# main_module.net
KiCad netlist of a schematic drawn in EAGLE
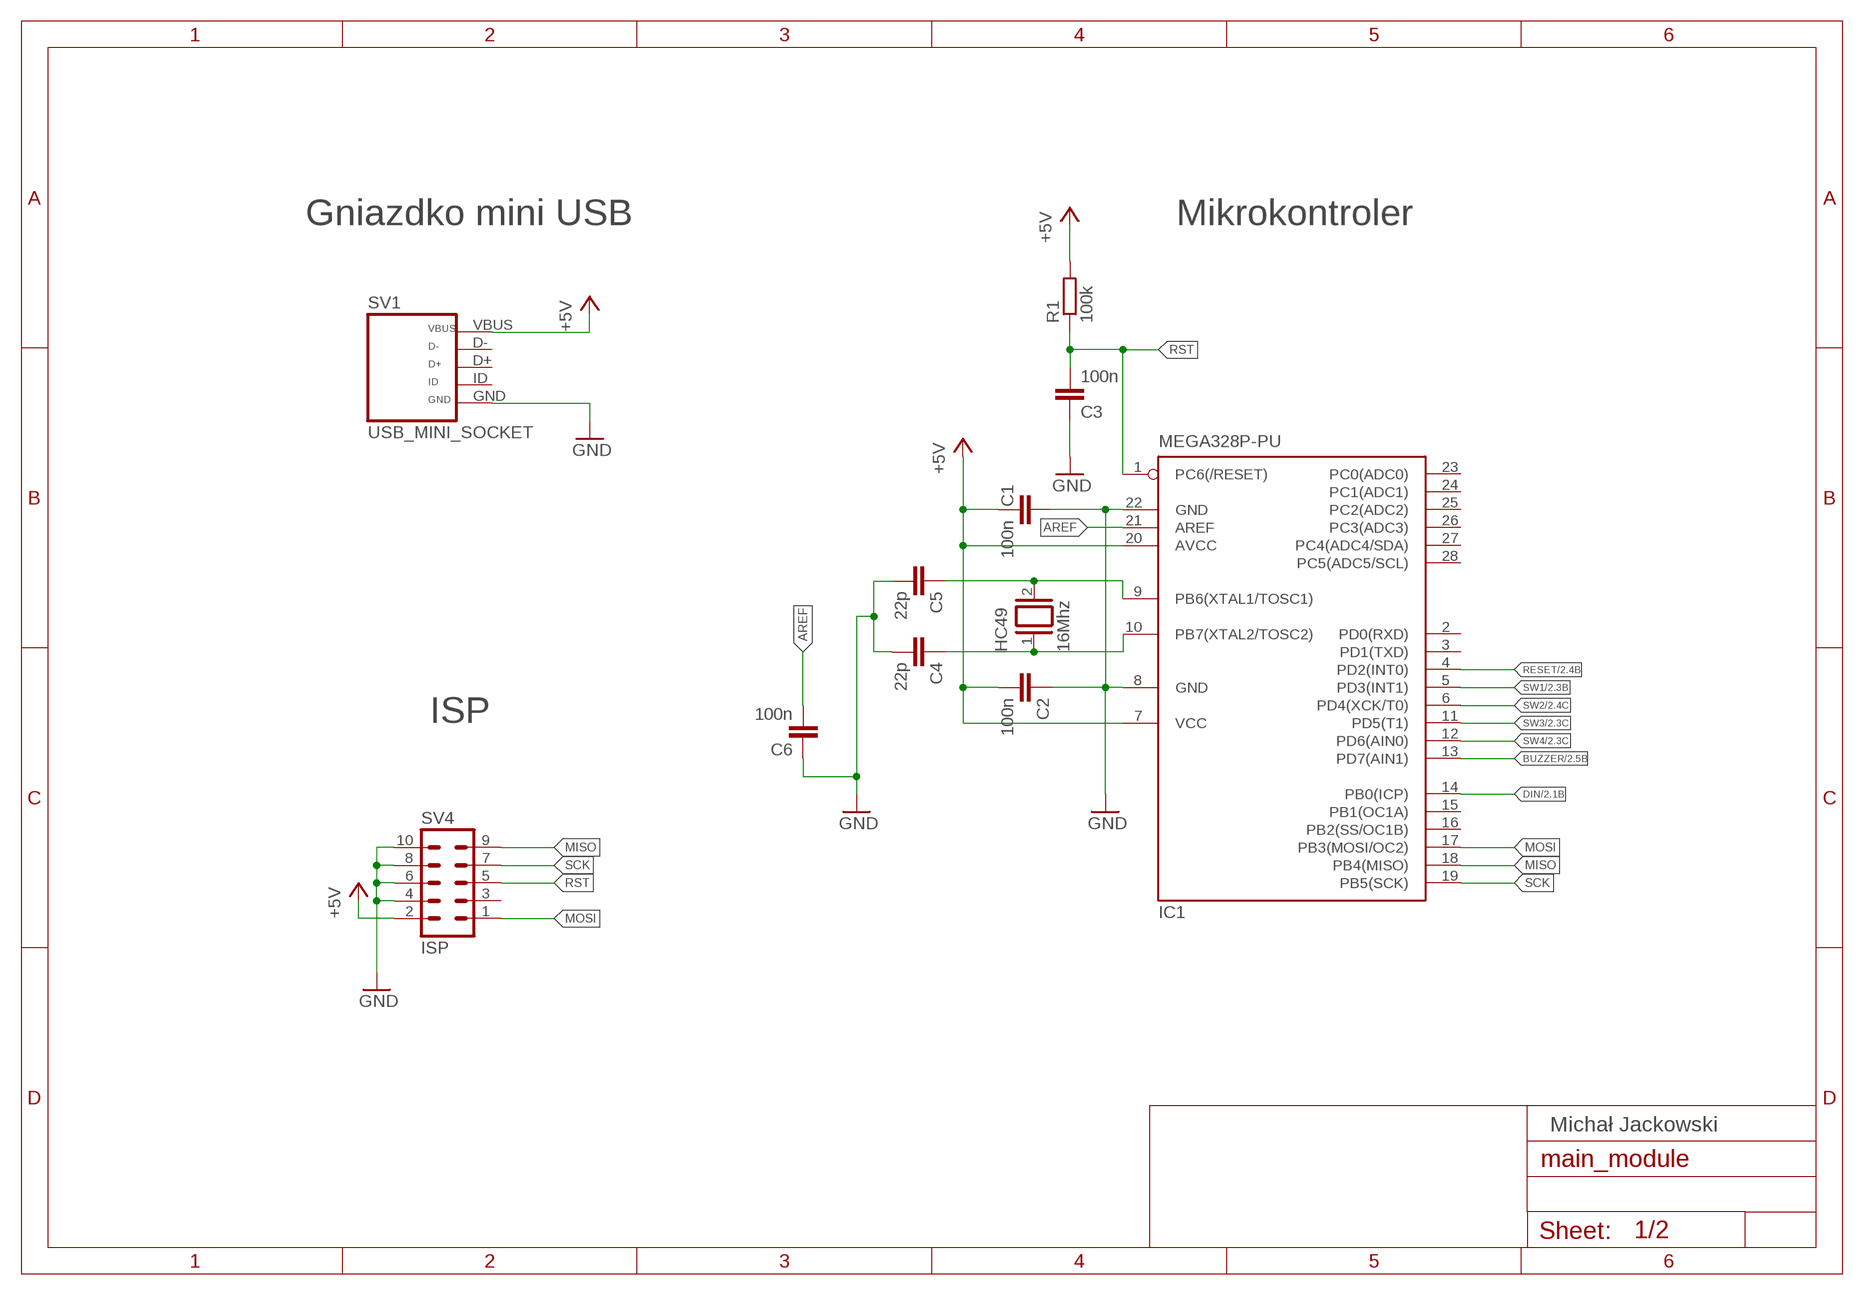
[diagram p0: schematic, sheet 1]
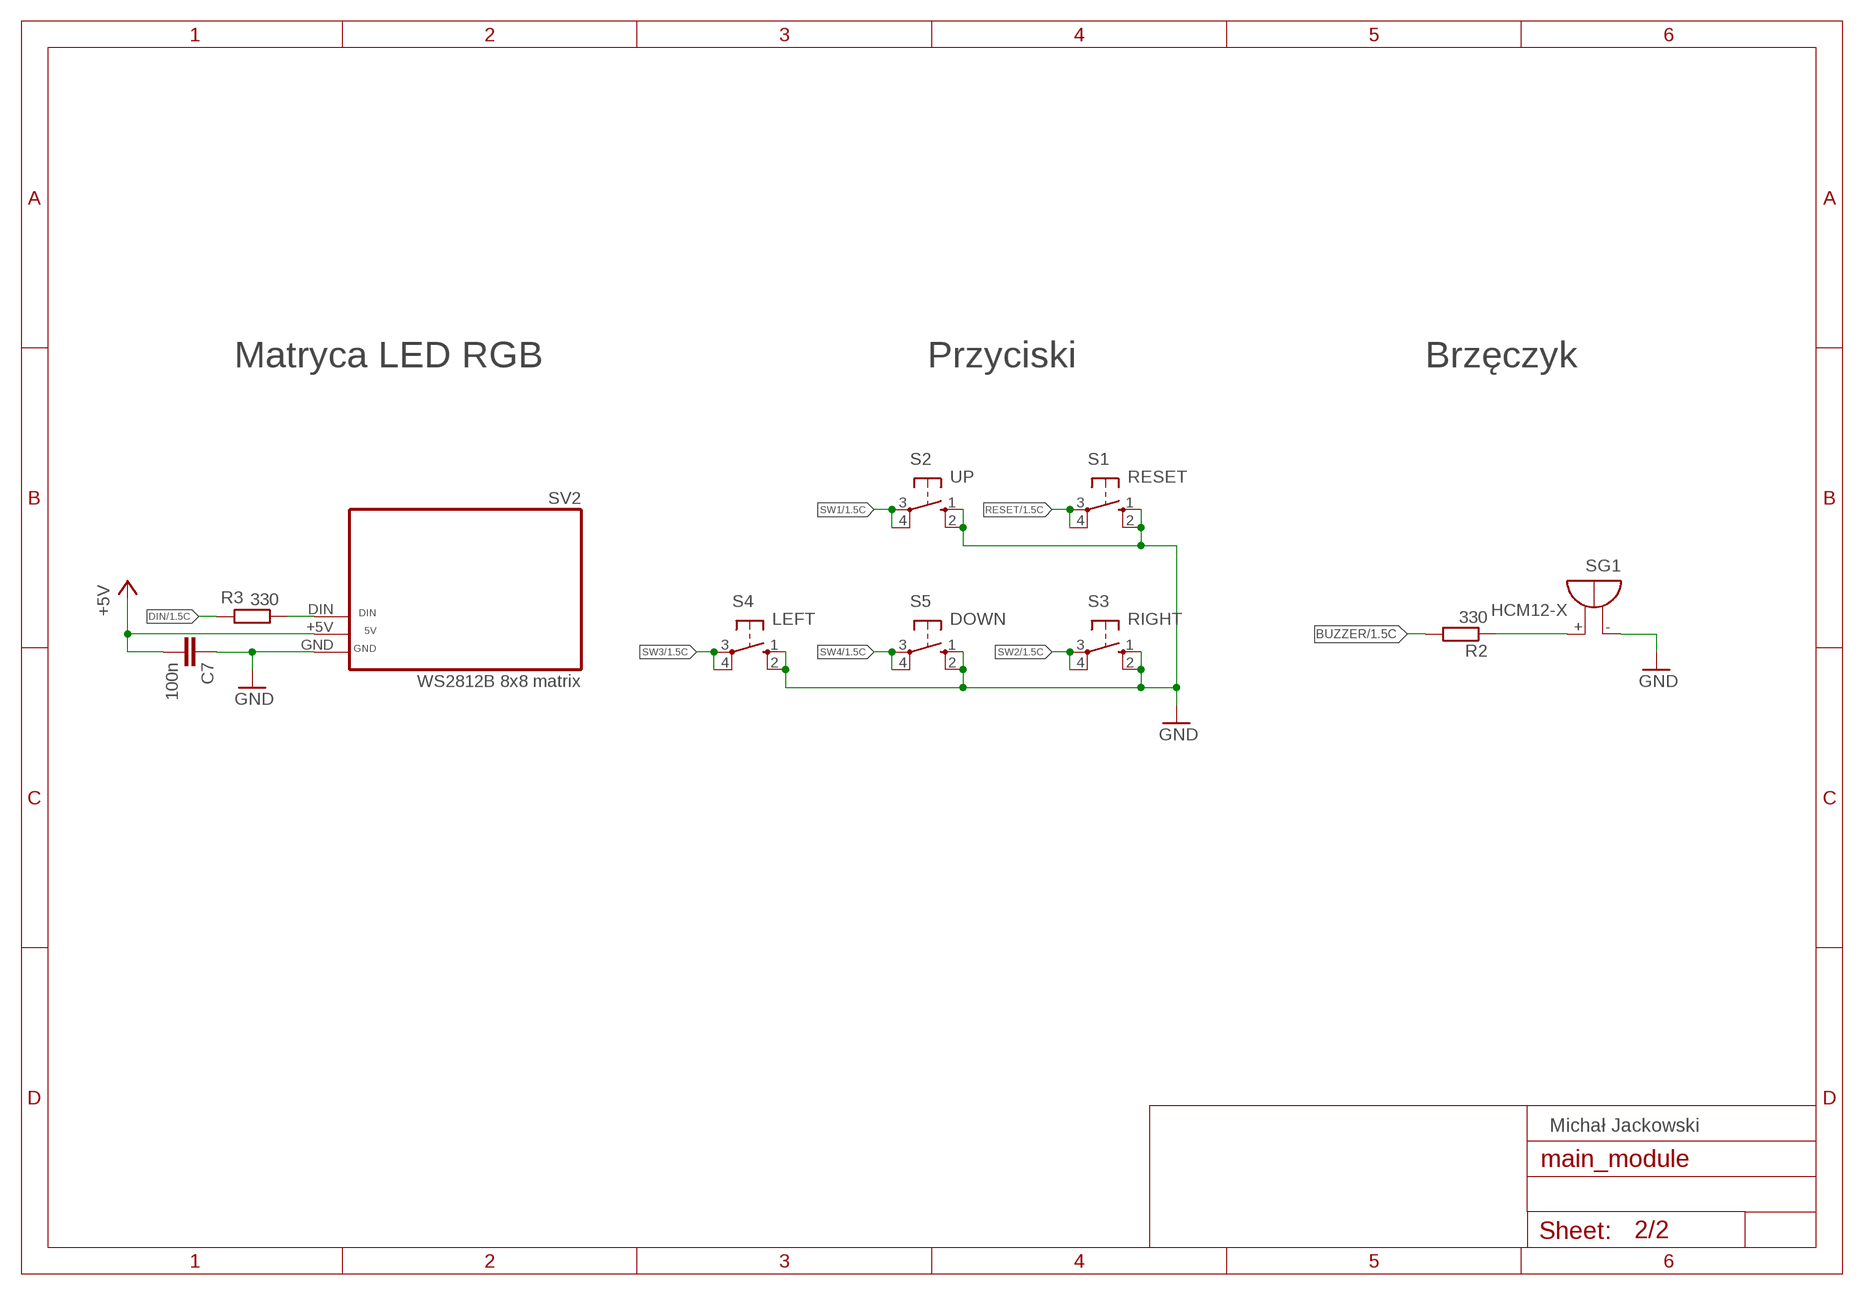
[diagram p1: schematic, sheet 2]

(export (version "E")
  (design (tool "Eeschema 10.0.6"))
  (components
    (comp (ref "C1")
      (value "100n")
      (footprint "eagle-import:C025-040X050")
      (libsource (lib "eagle-import") (part "C-EU025-040X050"))
    )
    (comp (ref "C2")
      (value "100n")
      (footprint "eagle-import:C025-040X050")
      (libsource (lib "eagle-import") (part "C-EU025-040X050"))
    )
    (comp (ref "C3")
      (value "100n")
      (footprint "eagle-import:C025-040X050")
      (libsource (lib "eagle-import") (part "C-EU025-040X050"))
    )
    (comp (ref "C4")
      (value "22p")
      (footprint "eagle-import:C025-040X050")
      (libsource (lib "eagle-import") (part "C-EU025-040X050"))
    )
    (comp (ref "C5")
      (value "22p")
      (footprint "eagle-import:C025-040X050")
      (libsource (lib "eagle-import") (part "C-EU025-040X050"))
    )
    (comp (ref "C6")
      (value "100n")
      (footprint "eagle-import:C025-040X050")
      (libsource (lib "eagle-import") (part "C-EU025-040X050"))
    )
    (comp (ref "IC1")
      (value "MEGA328P-PU")
      (footprint "eagle-import:DIL28-3")
      (libsource (lib "eagle-import") (part "MEGA328P-PU"))
    )
    (comp (ref "Q1")
      (value "16Mhz")
      (footprint "eagle-import:Q")
      (libsource (lib "eagle-import") (part "XTAL"))
    )
    (comp (ref "R1")
      (value "100k")
      (footprint "eagle-import:0204_7")
      (libsource (lib "eagle-import") (part "R-EU_0204/7"))
    )
    (comp (ref "SV1")
      (value "USB_MINI_SOCKET")
      (footprint "eagle-import:FE05-1")
      (libsource (lib "eagle-import") (part "USB_MINI_SOCKETGNIAZDO5PINFE"))
    )
    (comp (ref "SV4")
      (value "ISP")
      (footprint "eagle-import:ML10L")
      (libsource (lib "eagle-import") (part "ML10L"))
    )
    (comp (ref "C7")
      (value "100n")
      (footprint "eagle-import:C025-040X050")
      (libsource (lib "eagle-import") (part "C-EU025-040X050"))
    )
    (comp (ref "R2")
      (value "330")
      (footprint "eagle-import:0204_7")
      (libsource (lib "eagle-import") (part "R-EU_0204/7"))
    )
    (comp (ref "R3")
      (value "330")
      (footprint "eagle-import:0204_7")
      (libsource (lib "eagle-import") (part "R-EU_0204/7"))
    )
    (comp (ref "S1")
      (value "RESET")
      (footprint "eagle-import:B3F-40XX")
      (fields (field (name "MF") "OMRON COMPONENTS USA") (field (name "MPN") "B3F-4000"))
      (libsource (lib "eagle-import") (part "40-XX"))
    )
    (comp (ref "S2")
      (value "UP")
      (footprint "eagle-import:B3F-40XX")
      (fields (field (name "MF") "OMRON COMPONENTS USA") (field (name "MPN") "B3F-4000"))
      (libsource (lib "eagle-import") (part "40-XX"))
    )
    (comp (ref "S3")
      (value "RIGHT")
      (footprint "eagle-import:B3F-40XX")
      (fields (field (name "MF") "OMRON COMPONENTS USA") (field (name "MPN") "B3F-4000"))
      (libsource (lib "eagle-import") (part "40-XX"))
    )
    (comp (ref "S4")
      (value "LEFT")
      (footprint "eagle-import:B3F-40XX")
      (fields (field (name "MF") "OMRON COMPONENTS USA") (field (name "MPN") "B3F-4000"))
      (libsource (lib "eagle-import") (part "40-XX"))
    )
    (comp (ref "S5")
      (value "DOWN")
      (footprint "eagle-import:B3F-40XX")
      (fields (field (name "MF") "OMRON COMPONENTS USA") (field (name "MPN") "B3F-4000"))
      (libsource (lib "eagle-import") (part "40-XX"))
    )
    (comp (ref "SG1")
      (value "HCM12-X")
      (footprint "eagle-import:F_QMBIII")
      (libsource (lib "eagle-import") (part "HCM12-X"))
    )
    (comp (ref "SV2")
      (value "RGB_MATRIX_SOCKET")
      (footprint "eagle-import:MA03-1")
      (libsource (lib "eagle-import") (part "RGB_MATRIX_CONNECTOR"))
    )
  )
  (nets
    (net (code "1") (name "+5V") (class "Default")
      (node (ref "C1") (pin "2") (pinfunction "2_2") (pintype "passive"))
      (node (ref "C2") (pin "2") (pinfunction "2_2") (pintype "passive"))
      (node (ref "C7") (pin "2") (pinfunction "2_2") (pintype "passive"))
      (node (ref "IC1") (pin "20") (pinfunction "AVCC_20") (pintype "power_in"))
      (node (ref "IC1") (pin "7") (pinfunction "VCC_7") (pintype "power_in"))
      (node (ref "R1") (pin "2") (pinfunction "2_2") (pintype "passive"))
      (node (ref "SV1") (pin "VBUS") (pinfunction "VBUS_VBUS") (pintype "passive"))
      (node (ref "SV2") (pin "+5V") (pinfunction "5V_+5V") (pintype "passive"))
      (node (ref "SV4") (pin "2") (pinfunction "2_2") (pintype "passive"))
    )
    (net (code "2") (name "AREF") (class "Default")
      (node (ref "C6") (pin "2") (pinfunction "2_2") (pintype "passive"))
      (node (ref "IC1") (pin "21") (pinfunction "AREF_21") (pintype "passive"))
    )
    (net (code "3") (name "BUZZER") (class "Default")
      (node (ref "IC1") (pin "13") (pinfunction "PD7(AIN1)_13") (pintype "bidirectional"))
      (node (ref "R2") (pin "2") (pinfunction "2_2") (pintype "passive"))
    )
    (net (code "4") (name "DIN") (class "Default")
      (node (ref "IC1") (pin "14") (pinfunction "PB0(ICP)_14") (pintype "bidirectional"))
      (node (ref "R3") (pin "2") (pinfunction "2_2") (pintype "passive"))
    )
    (net (code "5") (name "GND") (class "Default")
      (node (ref "C1") (pin "1") (pinfunction "1_1") (pintype "passive"))
      (node (ref "C2") (pin "1") (pinfunction "1_1") (pintype "passive"))
      (node (ref "C3") (pin "1") (pinfunction "1_1") (pintype "passive"))
      (node (ref "C4") (pin "2") (pinfunction "2_2") (pintype "passive"))
      (node (ref "C5") (pin "2") (pinfunction "2_2") (pintype "passive"))
      (node (ref "C6") (pin "1") (pinfunction "1_1") (pintype "passive"))
      (node (ref "C7") (pin "1") (pinfunction "1_1") (pintype "passive"))
      (node (ref "IC1") (pin "22") (pinfunction "GND_22") (pintype "power_in"))
      (node (ref "IC1") (pin "8") (pinfunction "GND_8") (pintype "power_in"))
      (node (ref "S1") (pin "1") (pinfunction "S_1") (pintype "passive"))
      (node (ref "S1") (pin "2") (pinfunction "S1_2") (pintype "passive"))
      (node (ref "S2") (pin "1") (pinfunction "S_1") (pintype "passive"))
      (node (ref "S2") (pin "2") (pinfunction "S1_2") (pintype "passive"))
      (node (ref "S3") (pin "1") (pinfunction "S_1") (pintype "passive"))
      (node (ref "S3") (pin "2") (pinfunction "S1_2") (pintype "passive"))
      (node (ref "S4") (pin "1") (pinfunction "S_1") (pintype "passive"))
      (node (ref "S4") (pin "2") (pinfunction "S1_2") (pintype "passive"))
      (node (ref "S5") (pin "1") (pinfunction "S_1") (pintype "passive"))
      (node (ref "S5") (pin "2") (pinfunction "S1_2") (pintype "passive"))
      (node (ref "SG1") (pin "-") (pinfunction "+_-") (pintype "passive"))
      (node (ref "SV1") (pin "GND") (pinfunction "GND_GND") (pintype "passive"))
      (node (ref "SV2") (pin "GND") (pinfunction "GND_GND") (pintype "passive"))
      (node (ref "SV4") (pin "10") (pinfunction "10_10") (pintype "passive"))
      (node (ref "SV4") (pin "4") (pinfunction "4_4") (pintype "passive"))
      (node (ref "SV4") (pin "6") (pinfunction "6_6") (pintype "passive"))
      (node (ref "SV4") (pin "8") (pinfunction "8_8") (pintype "passive"))
    )
    (net (code "6") (name "MISO") (class "Default")
      (node (ref "IC1") (pin "18") (pinfunction "PB4(MISO)_18") (pintype "bidirectional"))
      (node (ref "SV4") (pin "9") (pinfunction "9_9") (pintype "passive"))
    )
    (net (code "7") (name "MOSI") (class "Default")
      (node (ref "IC1") (pin "17") (pinfunction "PB3(MOSI/OC2)_17") (pintype "bidirectional"))
      (node (ref "SV4") (pin "1") (pinfunction "1_1") (pintype "passive"))
    )
    (net (code "8") (name "Net-(IC1-PB6(XTAL1{slash}TOSC1))") (class "Default")
      (node (ref "C5") (pin "1") (pinfunction "1_1") (pintype "passive"))
      (node (ref "IC1") (pin "9") (pinfunction "PB6(XTAL1/TOSC1)_9") (pintype "bidirectional"))
      (node (ref "Q1") (pin "2") (pinfunction "2_2") (pintype "passive"))
    )
    (net (code "9") (name "Net-(IC1-PB7(XTAL2{slash}TOSC2))") (class "Default")
      (node (ref "C4") (pin "1") (pinfunction "1_1") (pintype "passive"))
      (node (ref "IC1") (pin "10") (pinfunction "PB7(XTAL2/TOSC2)_10") (pintype "bidirectional"))
      (node (ref "Q1") (pin "1") (pinfunction "1_1") (pintype "passive"))
    )
    (net (code "10") (name "Net-(R3-Pad1)") (class "Default")
      (node (ref "R3") (pin "1") (pinfunction "1_1") (pintype "passive"))
      (node (ref "SV2") (pin "DIN") (pinfunction "DIN_DIN") (pintype "passive"))
    )
    (net (code "11") (name "Net-(SG1--)") (class "Default")
      (node (ref "R2") (pin "1") (pinfunction "1_1") (pintype "passive"))
      (node (ref "SG1") (pin "+") (pinfunction "-_+") (pintype "passive"))
    )
    (net (code "12") (name "RESET") (class "Default")
      (node (ref "IC1") (pin "4") (pinfunction "PD2(INT0)_4") (pintype "bidirectional"))
      (node (ref "S1") (pin "3") (pinfunction "P_3") (pintype "passive"))
      (node (ref "S1") (pin "4") (pinfunction "P1_4") (pintype "passive"))
    )
    (net (code "13") (name "RST") (class "Default")
      (node (ref "C3") (pin "2") (pinfunction "2_2") (pintype "passive"))
      (node (ref "IC1") (pin "1") (pinfunction "PC6(/RESET)_1") (pintype "bidirectional"))
      (node (ref "R1") (pin "1") (pinfunction "1_1") (pintype "passive"))
      (node (ref "SV4") (pin "5") (pinfunction "5_5") (pintype "passive"))
    )
    (net (code "14") (name "SCK") (class "Default")
      (node (ref "IC1") (pin "19") (pinfunction "PB5(SCK)_19") (pintype "bidirectional"))
      (node (ref "SV4") (pin "7") (pinfunction "7_7") (pintype "passive"))
    )
    (net (code "15") (name "SW1") (class "Default")
      (node (ref "IC1") (pin "5") (pinfunction "PD3(INT1)_5") (pintype "bidirectional"))
      (node (ref "S2") (pin "3") (pinfunction "P_3") (pintype "passive"))
      (node (ref "S2") (pin "4") (pinfunction "P1_4") (pintype "passive"))
    )
    (net (code "16") (name "SW2") (class "Default")
      (node (ref "IC1") (pin "6") (pinfunction "PD4(XCK/T0)_6") (pintype "bidirectional"))
      (node (ref "S3") (pin "3") (pinfunction "P_3") (pintype "passive"))
      (node (ref "S3") (pin "4") (pinfunction "P1_4") (pintype "passive"))
    )
    (net (code "17") (name "SW3") (class "Default")
      (node (ref "IC1") (pin "11") (pinfunction "PD5(T1)_11") (pintype "bidirectional"))
      (node (ref "S4") (pin "3") (pinfunction "P_3") (pintype "passive"))
      (node (ref "S4") (pin "4") (pinfunction "P1_4") (pintype "passive"))
    )
    (net (code "18") (name "SW4") (class "Default")
      (node (ref "IC1") (pin "12") (pinfunction "PD6(AIN0)_12") (pintype "bidirectional"))
      (node (ref "S5") (pin "3") (pinfunction "P_3") (pintype "passive"))
      (node (ref "S5") (pin "4") (pinfunction "P1_4") (pintype "passive"))
    )
    (net (code "19") (name "unconnected-(IC1-PB1(OC1A)-Pad15)") (class "Default")
      (node (ref "IC1") (pin "15") (pinfunction "PB1(OC1A)_15") (pintype "bidirectional"))
    )
    (net (code "20") (name "unconnected-(IC1-PB2(SS{slash}OC1B)-Pad16)") (class "Default")
      (node (ref "IC1") (pin "16") (pinfunction "PB2(SS/OC1B)_16") (pintype "bidirectional"))
    )
    (net (code "21") (name "unconnected-(IC1-PC0(ADC0)-Pad23)") (class "Default")
      (node (ref "IC1") (pin "23") (pinfunction "PC0(ADC0)_23") (pintype "bidirectional"))
    )
    (net (code "22") (name "unconnected-(IC1-PC1(ADC1)-Pad24)") (class "Default")
      (node (ref "IC1") (pin "24") (pinfunction "PC1(ADC1)_24") (pintype "bidirectional"))
    )
    (net (code "23") (name "unconnected-(IC1-PC2(ADC2)-Pad25)") (class "Default")
      (node (ref "IC1") (pin "25") (pinfunction "PC2(ADC2)_25") (pintype "bidirectional"))
    )
    (net (code "24") (name "unconnected-(IC1-PC3(ADC3)-Pad26)") (class "Default")
      (node (ref "IC1") (pin "26") (pinfunction "PC3(ADC3)_26") (pintype "bidirectional"))
    )
    (net (code "25") (name "unconnected-(IC1-PC4(ADC4{slash}SDA)-Pad27)") (class "Default")
      (node (ref "IC1") (pin "27") (pinfunction "PC4(ADC4/SDA)_27") (pintype "bidirectional"))
    )
    (net (code "26") (name "unconnected-(IC1-PC5(ADC5{slash}SCL)-Pad28)") (class "Default")
      (node (ref "IC1") (pin "28") (pinfunction "PC5(ADC5/SCL)_28") (pintype "bidirectional"))
    )
    (net (code "27") (name "unconnected-(IC1-PD0(RXD)-Pad2)") (class "Default")
      (node (ref "IC1") (pin "2") (pinfunction "PD0(RXD)_2") (pintype "bidirectional"))
    )
    (net (code "28") (name "unconnected-(IC1-PD1(TXD)-Pad3)") (class "Default")
      (node (ref "IC1") (pin "3") (pinfunction "PD1(TXD)_3") (pintype "bidirectional"))
    )
    (net (code "29") (name "unconnected-(SV1-PadD+)") (class "Default")
      (node (ref "SV1") (pin "D+") (pinfunction "D+_D+") (pintype "passive"))
    )
    (net (code "30") (name "unconnected-(SV1-PadD-)") (class "Default")
      (node (ref "SV1") (pin "D-") (pinfunction "D-_D-") (pintype "passive"))
    )
    (net (code "31") (name "unconnected-(SV1-PadID)") (class "Default")
      (node (ref "SV1") (pin "ID") (pinfunction "ID_ID") (pintype "passive"))
    )
    (net (code "32") (name "unconnected-(SV4-Pad3)") (class "Default")
      (node (ref "SV4") (pin "3") (pinfunction "3_3") (pintype "passive"))
    )
  )
)
